# ESQUEMATICO_SENSOR_RPM.net
KiCad netlist of a schematic drawn in Altium Designer
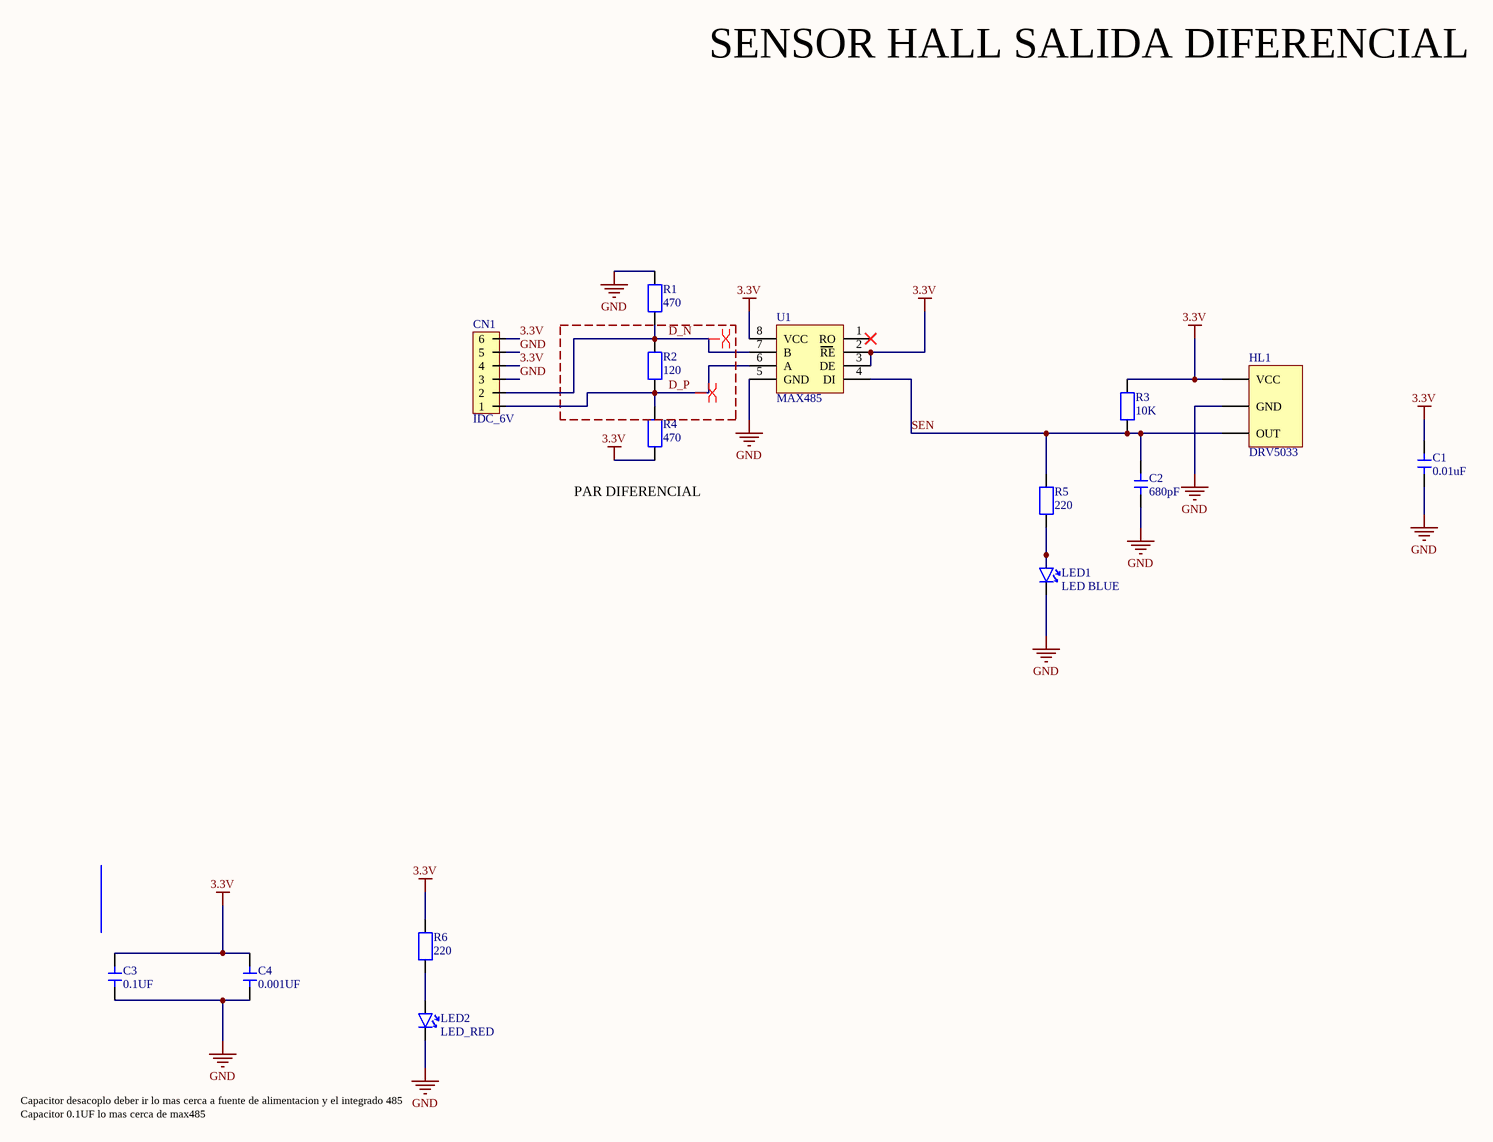
[diagram p0: ESQUEMATICO SENSOR RPM.SchDoc]

(export (version "E")
  (design (tool "Eeschema 10.0.6"))
  (components
    (comp (ref "C1") (value "0.01uF") (footprint "C0805") (libsource (lib "SCHLIB 485") (part "CAP0805")))
    (comp (ref "C2") (value "680pF") (footprint "C0805") (libsource (lib "SCHLIB 485") (part "CAP0805")))
    (comp (ref "C3") (value "0.1UF") (footprint "C0805") (libsource (lib "SCHLIB 485") (part "CAP0805")))
    (comp (ref "C4") (value "0.001UF") (footprint "C0805") (libsource (lib "SCHLIB 485") (part "CAP0805")))
    (comp (ref "CN1")
      (value "IDC_6V")
      (footprint "IDC_MALE_6V")
      (libsource (lib "SCHLIB 485") (part "IDC_MALE_6V"))
    )
    (comp (ref "HL1") (value "DRV5033") (footprint "DRV5033") (libsource (lib "SCHLIB 485") (part "DRV5033")))
    (comp (ref "LED1")
      (value "LED BLUE")
      (footprint "LED0805")
      (description "LED 0805")
      (libsource (lib "SCHLIB 485") (part "LED0805"))
    )
    (comp (ref "LED2")
      (value "LED_RED")
      (footprint "LED0805")
      (description "LED 0805")
      (libsource (lib "SCHLIB 485") (part "LED0805"))
    )
    (comp (ref "R1") (value "470") (footprint "R0805") (libsource (lib "SCHLIB 485") (part "R0805")))
    (comp (ref "R2") (value "120") (footprint "R0805") (libsource (lib "SCHLIB 485") (part "R0805")))
    (comp (ref "R3") (value "10K") (footprint "R0805") (libsource (lib "SCHLIB 485") (part "R0805")))
    (comp (ref "R4") (value "470") (footprint "R0805") (libsource (lib "SCHLIB 485") (part "R0805")))
    (comp (ref "R5") (value "220") (footprint "R0805") (libsource (lib "SCHLIB 485") (part "R0805")))
    (comp (ref "R6") (value "220") (footprint "R0805") (libsource (lib "SCHLIB 485") (part "R0805")))
    (comp (ref "U1") (value "MAX485") (footprint "IC485") (libsource (lib "SCHLIB 485") (part "IC485")))
  )
  (nets
    (net (code "1") (name "/D_N") (class "Default")
      (node (ref "CN1") (pin "2") (pinfunction "2_2") (pintype "passive"))
      (node (ref "R1") (pin "1") (pinfunction "1_1") (pintype "passive"))
      (node (ref "R2") (pin "2") (pinfunction "2_2") (pintype "passive"))
      (node (ref "U1") (pin "7") (pinfunction "B_7") (pintype "passive"))
    )
    (net (code "2") (name "/D_P") (class "Default")
      (node (ref "CN1") (pin "1") (pinfunction "1_1") (pintype "passive"))
      (node (ref "R2") (pin "1") (pinfunction "1_1") (pintype "passive"))
      (node (ref "R4") (pin "2") (pinfunction "2_2") (pintype "passive"))
      (node (ref "U1") (pin "6") (pinfunction "A_6") (pintype "passive"))
    )
    (net (code "3") (name "/SEN") (class "Default")
      (node (ref "C2") (pin "2") (pinfunction "2_2") (pintype "passive"))
      (node (ref "HL1") (pin "3") (pinfunction "OUT_3") (pintype "passive"))
      (node (ref "R3") (pin "1") (pinfunction "1_1") (pintype "passive"))
      (node (ref "R5") (pin "2") (pinfunction "2_2") (pintype "passive"))
      (node (ref "U1") (pin "4") (pinfunction "DI_4") (pintype "passive"))
    )
    (net (code "4") (name "3.3V") (class "Default")
      (node (ref "C1") (pin "2") (pinfunction "2_2") (pintype "passive"))
      (node (ref "C3") (pin "2") (pinfunction "2_2") (pintype "passive"))
      (node (ref "C4") (pin "2") (pinfunction "2_2") (pintype "passive"))
      (node (ref "CN1") (pin "4") (pinfunction "4_4") (pintype "passive"))
      (node (ref "CN1") (pin "6") (pinfunction "6_6") (pintype "passive"))
      (node (ref "HL1") (pin "1") (pinfunction "VCC_1") (pintype "passive"))
      (node (ref "R3") (pin "2") (pinfunction "2_2") (pintype "passive"))
      (node (ref "R4") (pin "1") (pinfunction "1_1") (pintype "passive"))
      (node (ref "R6") (pin "2") (pinfunction "2_2") (pintype "passive"))
      (node (ref "U1") (pin "2") (pinfunction "RE_2") (pintype "passive"))
      (node (ref "U1") (pin "3") (pinfunction "DE_3") (pintype "passive"))
      (node (ref "U1") (pin "8") (pinfunction "VCC_8") (pintype "passive"))
    )
    (net (code "5") (name "GND") (class "Default")
      (node (ref "C1") (pin "1") (pinfunction "1_1") (pintype "passive"))
      (node (ref "C2") (pin "1") (pinfunction "1_1") (pintype "passive"))
      (node (ref "C3") (pin "1") (pinfunction "1_1") (pintype "passive"))
      (node (ref "C4") (pin "1") (pinfunction "1_1") (pintype "passive"))
      (node (ref "CN1") (pin "3") (pinfunction "3_3") (pintype "passive"))
      (node (ref "CN1") (pin "5") (pinfunction "5_5") (pintype "passive"))
      (node (ref "HL1") (pin "2") (pinfunction "GND_2") (pintype "passive"))
      (node (ref "LED1") (pin "2") (pinfunction "C_2") (pintype "passive"))
      (node (ref "LED2") (pin "2") (pinfunction "C_2") (pintype "passive"))
      (node (ref "R1") (pin "2") (pinfunction "2_2") (pintype "passive"))
      (node (ref "U1") (pin "5") (pinfunction "GND_5") (pintype "passive"))
    )
    (net (code "6") (name "Net-(LED1-A)") (class "Default")
      (node (ref "LED1") (pin "1") (pinfunction "A_1") (pintype "passive"))
      (node (ref "R5") (pin "1") (pinfunction "1_1") (pintype "passive"))
    )
    (net (code "7") (name "Net-(LED2-A)") (class "Default")
      (node (ref "LED2") (pin "1") (pinfunction "A_1") (pintype "passive"))
      (node (ref "R6") (pin "1") (pinfunction "1_1") (pintype "passive"))
    )
    (net (code "8") (name "unconnected-(U1-RO-Pad1)") (class "Default")
      (node (ref "U1") (pin "1") (pinfunction "RO_1") (pintype "passive+no_connect"))
    )
  )
)
